# Page-3.net
KiCad netlist of a schematic drawn in Altium Designer
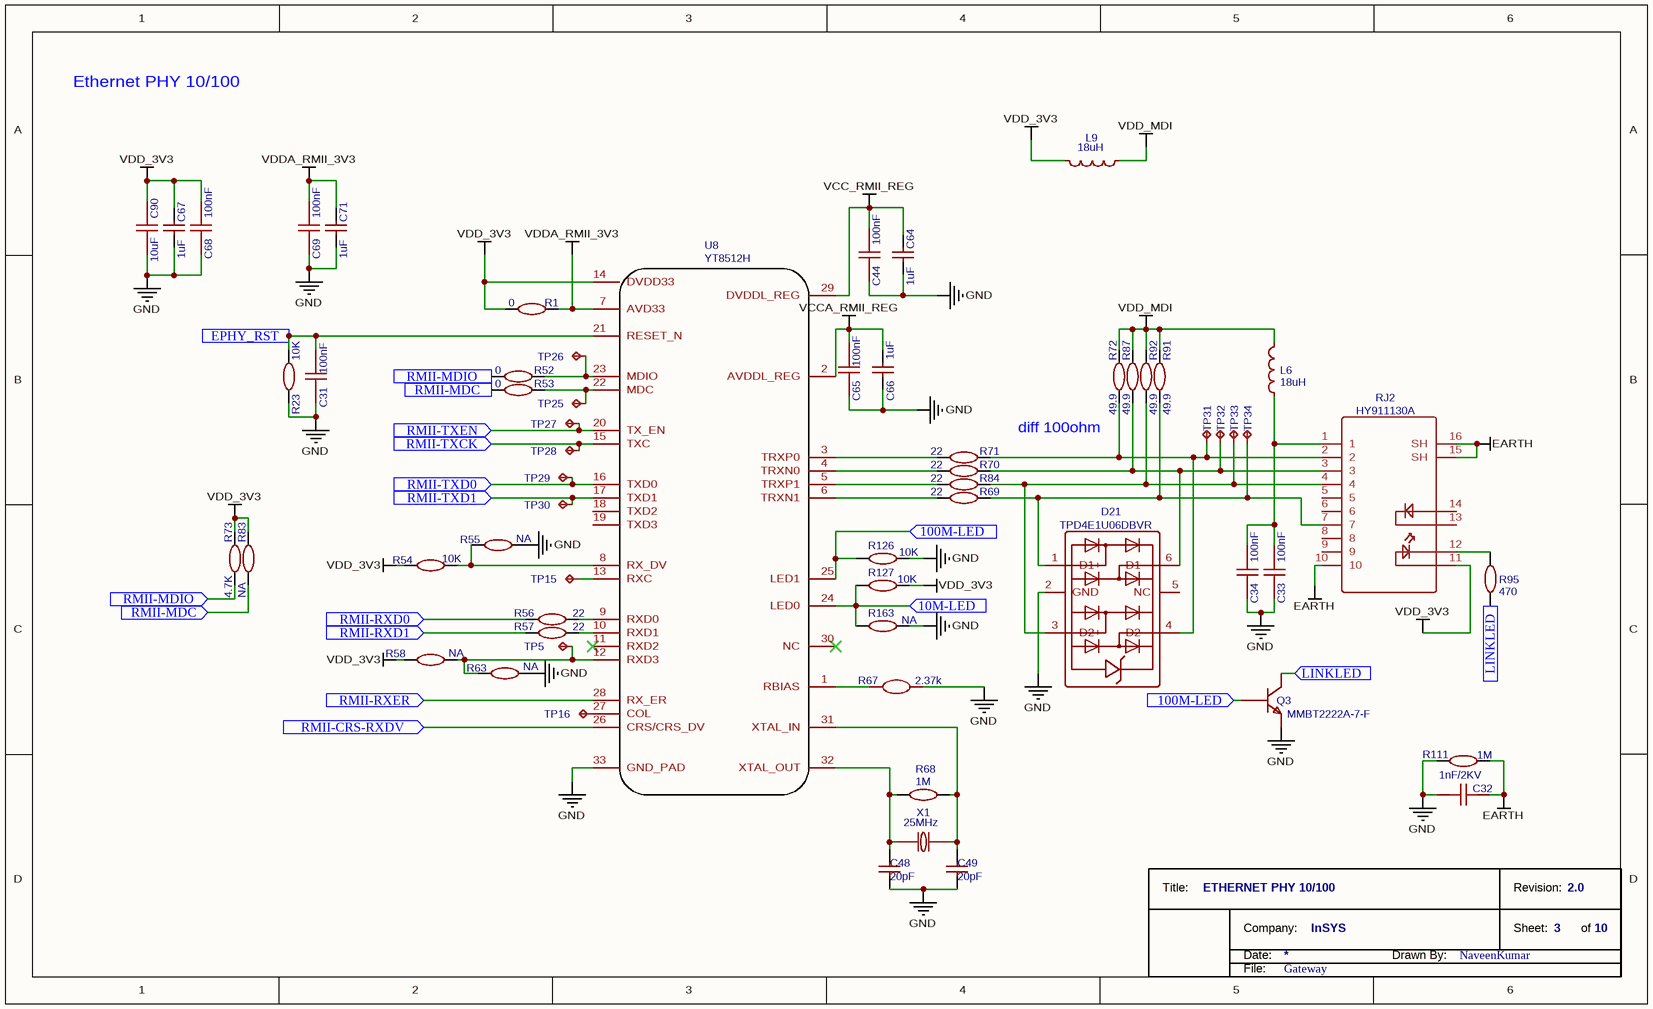
[diagram p0: Page-3.schdoc]

(export (version "E")
  (design (tool "Eeschema 10.0.6"))
  (components
    (comp (ref "*")
      (value "TitleBlock_1")
      (description "TitleBlock  No-2")
      (fields (field (name "DRAWN BY") "*"))
      (libsource (lib "GateWay_AllwinnerV2") (part "TitleBlock_1"))
    )
    (comp (ref "C31")
      (value "100nF")
      (footprint "GWAY_Capacitor_0603")
      (fields (field (name "MANUFACTURER") "SAMSUNG") (field (name "MANUFACTURER PART") "CL10B104KB8NNNC"))
      (libsource (lib "altium-import") (part "root_3_100nF_"))
    )
    (comp (ref "C32")
      (value "1nF/2KV")
      (footprint "GWAY_Capacitor_1206")
      (fields
        (field (name "MANUFACTURER") "Walsin Tech Corp")
        (field (name "MANUFACTURER PART") "1206B102K202CT")
        (field (name "CONTRIBUTOR") "LCSC")
      )
      (libsource (lib "altium-import") (part "root_0_1nF/2KV_"))
    )
    (comp (ref "C33")
      (value "100nF")
      (footprint "GWAY_Capacitor_0603")
      (fields (field (name "MANUFACTURER") "SAMSUNG") (field (name "MANUFACTURER PART") "CL10B104KB8NNNC"))
      (libsource (lib "altium-import") (part "root_3_100nF_"))
    )
    (comp (ref "C34")
      (value "100nF")
      (footprint "GWAY_Capacitor_0603")
      (fields (field (name "MANUFACTURER") "SAMSUNG") (field (name "MANUFACTURER PART") "CL10B104KB8NNNC"))
      (libsource (lib "altium-import") (part "root_3_100nF_"))
    )
    (comp (ref "C44")
      (value "100nF")
      (footprint "GWAY_Capacitor_0603")
      (fields (field (name "MANUFACTURER") "SAMSUNG") (field (name "MANUFACTURER PART") "CL10B104KB8NNNC"))
      (libsource (lib "altium-import") (part "root_3_100nF_"))
    )
    (comp (ref "C48")
      (value "20pF")
      (footprint "GWAY_Capacitor_0603")
      (fields (field (name "MANUFACTURER PART") "CL10C200JB8NNNC") (field (name "MANUFACTURER") "SAMSUNG"))
      (libsource (lib "altium-import") (part "root_1_20pF_"))
    )
    (comp (ref "C49")
      (value "20pF")
      (footprint "GWAY_Capacitor_0603")
      (fields (field (name "MANUFACTURER PART") "CL10C200JB8NNNC") (field (name "MANUFACTURER") "SAMSUNG"))
      (libsource (lib "altium-import") (part "root_1_20pF_"))
    )
    (comp (ref "C64")
      (value "1uF")
      (footprint "GWAY_Capacitor_0603")
      (fields
        (field (name "MANUFACTURER PART") "CL10B105KA8NNNC")
        (field (name "MANUFACTURER") "SAMSUNG(三星)")
      )
      (libsource (lib "altium-import") (part "root_3_1uF_"))
    )
    (comp (ref "C65")
      (value "100nF")
      (footprint "GWAY_Capacitor_0603")
      (fields (field (name "MANUFACTURER") "SAMSUNG") (field (name "MANUFACTURER PART") "CL10B104KB8NNNC"))
      (libsource (lib "altium-import") (part "root_3_100nF_"))
    )
    (comp (ref "C66")
      (value "1uF")
      (footprint "GWAY_Capacitor_0603")
      (fields (field (name "MANUFACTURER PART") "CL10A105KO8NNNC") (field (name "MANUFACTURER") "SAMSUNG"))
      (libsource (lib "altium-import") (part "root_1_1uF_"))
    )
    (comp (ref "C67")
      (value "1uF")
      (footprint "GWAY_Capacitor_0603")
      (fields
        (field (name "MANUFACTURER PART") "CL10B105KA8NNNC")
        (field (name "MANUFACTURER") "SAMSUNG(三星)")
      )
      (libsource (lib "altium-import") (part "root_3_1uF_"))
    )
    (comp (ref "C68")
      (value "100nF")
      (footprint "GWAY_Capacitor_0603")
      (fields (field (name "MANUFACTURER") "SAMSUNG") (field (name "MANUFACTURER PART") "CL10B104KB8NNNC"))
      (libsource (lib "altium-import") (part "root_3_100nF_"))
    )
    (comp (ref "C69")
      (value "100nF")
      (footprint "GWAY_Capacitor_0603")
      (fields (field (name "MANUFACTURER") "SAMSUNG") (field (name "MANUFACTURER PART") "CL10B104KB8NNNC"))
      (libsource (lib "altium-import") (part "root_3_100nF_"))
    )
    (comp (ref "C71")
      (value "1uF")
      (footprint "GWAY_Capacitor_0603")
      (fields
        (field (name "MANUFACTURER PART") "CL10B105KA8NNNC")
        (field (name "MANUFACTURER") "SAMSUNG(三星)")
      )
      (libsource (lib "altium-import") (part "root_3_1uF_"))
    )
    (comp (ref "C90")
      (value "10uF")
      (footprint "GWAY_Capacitor_0805")
      (fields
        (field (name "MANUFACTURER") "SAMSUNG(三星)")
        (field (name "MANUFACTURER PART") "CL21B106KOQNNNE")
      )
      (libsource (lib "altium-import") (part "root_1_10uF_"))
    )
    (comp (ref "D21")
      (value "TPD4E1U06DBVR")
      (footprint "GWAY_SOT23-6PIN")
      (fields (field (name "MANUFACTURER") "TI(德州仪器)") (field (name "CONTRIBUTOR") "LCSC"))
      (libsource (lib "altium-import") (part "root_3_TPD4E1U06DBVR_"))
    )
    (comp (ref "L6")
      (value "18uH")
      (footprint "GWAY_FerriteeBEAD_0805_C2012X105N")
      (fields (field (name "MANUFACTURER PART") "MLI2012-180") (field (name "MANUFACTURER") "ReliaPro"))
      (libsource (lib "altium-import") (part "root_1_18uH_"))
    )
    (comp (ref "L9")
      (value "18uH")
      (footprint "GWAY_FerriteeBEAD_0805_C2012X105N")
      (fields (field (name "MANUFACTURER PART") "MLI2012-180") (field (name "MANUFACTURER") "ReliaPro"))
      (libsource (lib "altium-import") (part "root_2_18uH_"))
    )
    (comp (ref "Q3")
      (value "MMBT2222A-7-F")
      (footprint "GWAY_SOT23-3PIN")
      (fields (field (name "MANUFACTURER") "DIODES(美台)") (field (name "CONTRIBUTOR") "LCSC"))
      (libsource (lib "altium-import") (part "root_0_MMBT2222A-7-F_"))
    )
    (comp (ref "R1")
      (value "0")
      (footprint "GWAY_Resistor_0603")
      (fields (field (name "MANUFACTURER") "YAGEO") (field (name "MANUFACTURER PART") "RC0603FR-070RL"))
      (libsource (lib "altium-import") (part "root_2_0_"))
    )
    (comp (ref "R23")
      (value "10K")
      (footprint "GWAY_Resistor_0603")
      (fields (field (name "MANUFACTURER") "YAGEO") (field (name "MANUFACTURER PART") "RC0603JR-0710KL"))
      (libsource (lib "altium-import") (part "root_3_10K_"))
    )
    (comp (ref "R52")
      (value "0")
      (footprint "GWAY_Resistor_0603")
      (fields (field (name "MANUFACTURER") "YAGEO") (field (name "MANUFACTURER PART") "RC0603FR-070RL"))
      (libsource (lib "altium-import") (part "root_2_0_"))
    )
    (comp (ref "R53")
      (value "0")
      (footprint "GWAY_Resistor_0603")
      (fields (field (name "MANUFACTURER") "YAGEO") (field (name "MANUFACTURER PART") "RC0603FR-070RL"))
      (libsource (lib "altium-import") (part "root_2_0_"))
    )
    (comp (ref "R54")
      (value "10K")
      (footprint "GWAY_Resistor_0603")
      (fields (field (name "MANUFACTURER") "YAGEO") (field (name "MANUFACTURER PART") "RC0603JR-0710KL"))
      (libsource (lib "altium-import") (part "root_0_10K_"))
    )
    (comp (ref "R55")
      (value "NA")
      (footprint "GWAY_Resistor_0603")
      (fields (field (name "MANUFACTURER") "YAGEO") (field (name "MANUFACTURER PART") "RC0603JR-0710KL"))
      (libsource (lib "altium-import") (part "root_0_NA_"))
    )
    (comp (ref "R56")
      (value "22")
      (footprint "GWAY_Resistor_0603")
      (fields (field (name "MANUFACTURER") "YAGEO") (field (name "MANUFACTURER PART") "RC0603FR-0722RL"))
      (libsource (lib "altium-import") (part "root_0_22_"))
    )
    (comp (ref "R57")
      (value "22")
      (footprint "GWAY_Resistor_0603")
      (fields (field (name "MANUFACTURER") "YAGEO") (field (name "MANUFACTURER PART") "RC0603FR-0722RL"))
      (libsource (lib "altium-import") (part "root_0_22_"))
    )
    (comp (ref "R58")
      (value "NA")
      (footprint "GWAY_Resistor_0603")
      (fields (field (name "MANUFACTURER") "YAGEO") (field (name "MANUFACTURER PART") "RC0603JR-0710KL"))
      (libsource (lib "altium-import") (part "root_0_NA_"))
    )
    (comp (ref "R63")
      (value "NA")
      (footprint "GWAY_Resistor_0603")
      (fields (field (name "MANUFACTURER") "YAGEO") (field (name "MANUFACTURER PART") "RC0603JR-0710KL"))
      (libsource (lib "altium-import") (part "root_0_NA_"))
    )
    (comp (ref "R67")
      (value "2.37k")
      (footprint "GWAY_Resistor_0603")
      (fields
        (field (name "MANUFACTURER") "YAGEO(国巨)")
        (field (name "MANUFACTURER PART") "RC0603FR-072K37L")
        (field (name "CONTRIBUTOR") "LCSC")
      )
      (libsource (lib "altium-import") (part "root_0_2.37k_"))
    )
    (comp (ref "R68")
      (value "1M")
      (footprint "GWAY_Resistor_0603")
      (fields (field (name "MANUFACTURER") "YAGEO(国巨)") (field (name "MANUFACTURER PART") "AC0603FR-071ML"))
      (libsource (lib "altium-import") (part "root_0_1M_"))
    )
    (comp (ref "R69")
      (value "22")
      (footprint "GWAY_Resistor_0603")
      (fields (field (name "MANUFACTURER") "YAGEO") (field (name "MANUFACTURER PART") "RC0603FR-0722RL"))
      (libsource (lib "altium-import") (part "root_0_22_"))
    )
    (comp (ref "R70")
      (value "22")
      (footprint "GWAY_Resistor_0603")
      (fields (field (name "MANUFACTURER") "YAGEO") (field (name "MANUFACTURER PART") "RC0603FR-0722RL"))
      (libsource (lib "altium-import") (part "root_0_22_"))
    )
    (comp (ref "R71")
      (value "22")
      (footprint "GWAY_Resistor_0603")
      (fields (field (name "MANUFACTURER") "YAGEO") (field (name "MANUFACTURER PART") "RC0603FR-0722RL"))
      (libsource (lib "altium-import") (part "root_0_22_"))
    )
    (comp (ref "R72")
      (value "49.9")
      (footprint "GWAY_Resistor_0603")
      (fields (field (name "MANUFACTURER") "YAGEO(国巨)") (field (name "MANUFACTURER PART") "RC0603FR-0749R9L"))
      (libsource (lib "altium-import") (part "root_1_49.9_"))
    )
    (comp (ref "R73")
      (value "4.7K")
      (footprint "GWAY_Resistor_0603")
      (fields (field (name "MANUFACTURER") "YAGEO(国巨)") (field (name "MANUFACTURER PART") "RC0603FR-074K7L"))
      (libsource (lib "altium-import") (part "root_1_4.7K_"))
    )
    (comp (ref "R83")
      (value "NA")
      (footprint "GWAY_Resistor_0603")
      (fields (field (name "MANUFACTURER") "YAGEO(国巨)") (field (name "MANUFACTURER PART") "RC0603FR-074K7L"))
      (libsource (lib "altium-import") (part "root_1_NA_"))
    )
    (comp (ref "R84")
      (value "22")
      (footprint "GWAY_Resistor_0603")
      (fields (field (name "MANUFACTURER") "YAGEO") (field (name "MANUFACTURER PART") "RC0603FR-0722RL"))
      (libsource (lib "altium-import") (part "root_0_22_"))
    )
    (comp (ref "R87")
      (value "49.9")
      (footprint "GWAY_Resistor_0603")
      (fields (field (name "MANUFACTURER") "YAGEO(国巨)") (field (name "MANUFACTURER PART") "RC0603FR-0749R9L"))
      (libsource (lib "altium-import") (part "root_1_49.9_"))
    )
    (comp (ref "R91")
      (value "49.9")
      (footprint "GWAY_Resistor_0603")
      (fields (field (name "MANUFACTURER") "YAGEO(国巨)") (field (name "MANUFACTURER PART") "RC0603FR-0749R9L"))
      (libsource (lib "altium-import") (part "root_1_49.9_"))
    )
    (comp (ref "R92")
      (value "49.9")
      (footprint "GWAY_Resistor_0603")
      (fields (field (name "MANUFACTURER") "YAGEO(国巨)") (field (name "MANUFACTURER PART") "RC0603FR-0749R9L"))
      (libsource (lib "altium-import") (part "root_1_49.9_"))
    )
    (comp (ref "R95")
      (value "470")
      (footprint "GWAY_Resistor_0603")
      (fields (field (name "MANUFACTURER") "YAGEO") (field (name "MANUFACTURER PART") "RC0603FR-07470RL"))
      (libsource (lib "altium-import") (part "root_1_470_"))
    )
    (comp (ref "R111")
      (value "1M")
      (footprint "GWAY_Resistor_0603")
      (fields (field (name "MANUFACTURER") "YAGEO") (field (name "MANUFACTURER PART") "RC0603FR-071ML"))
      (libsource (lib "altium-import") (part "root_0_1M_"))
    )
    (comp (ref "R126")
      (value "10K")
      (footprint "GWAY_Resistor_0603")
      (fields (field (name "MANUFACTURER") "YAGEO") (field (name "MANUFACTURER PART") "RC0603JR-0710KL"))
      (libsource (lib "altium-import") (part "root_0_10K_"))
    )
    (comp (ref "R127")
      (value "10K")
      (footprint "GWAY_Resistor_0603")
      (fields (field (name "MANUFACTURER") "YAGEO") (field (name "MANUFACTURER PART") "RC0603JR-0710KL"))
      (libsource (lib "altium-import") (part "root_0_10K_"))
    )
    (comp (ref "R163")
      (value "NA")
      (footprint "GWAY_Resistor_0603")
      (fields (field (name "MANUFACTURER") "YAGEO") (field (name "MANUFACTURER PART") "RC0603JR-0710KL"))
      (libsource (lib "altium-import") (part "root_0_NA_"))
    )
    (comp (ref "RJ2")
      (value "HY911130A")
      (footprint "GWay_HY911130AE")
      (fields (field (name "MANUFACTURER") "HANRUN(汉仁)"))
      (libsource (lib "altium-import") (part "root_0_HY911130A_"))
    )
    (comp (ref "TP5")
      (value "TP-052-TJ")
      (footprint "GWAY_TESTPOINT1")
      (fields (field (name "MANUFACTURER PART") "?"))
      (libsource (lib "altium-import") (part "root_1_TP-052-TJ_"))
    )
    (comp (ref "TP15")
      (value "TP-052-TJ")
      (footprint "GWAY_TESTPOINT1")
      (fields (field (name "MANUFACTURER PART") "?"))
      (libsource (lib "altium-import") (part "root_1_TP-052-TJ_"))
    )
    (comp (ref "TP16")
      (value "TP-052-TJ")
      (footprint "GWAY_TESTPOINT1")
      (fields (field (name "MANUFACTURER PART") "?"))
      (libsource (lib "altium-import") (part "root_1_TP-052-TJ_"))
    )
    (comp (ref "TP25")
      (value "TP-052-TJ")
      (footprint "GWAY_TESTPOINT1")
      (fields (field (name "MANUFACTURER PART") "?"))
      (libsource (lib "altium-import") (part "root_1_TP-052-TJ_"))
    )
    (comp (ref "TP26")
      (value "TP-052-TJ")
      (footprint "GWAY_TESTPOINT1")
      (fields (field (name "MANUFACTURER PART") "?"))
      (libsource (lib "altium-import") (part "root_1_TP-052-TJ_"))
    )
    (comp (ref "TP27")
      (value "TP-052-TJ")
      (footprint "GWAY_TESTPOINT1")
      (fields (field (name "MANUFACTURER PART") "?"))
      (libsource (lib "altium-import") (part "root_1_TP-052-TJ_"))
    )
    (comp (ref "TP28")
      (value "TP-052-TJ")
      (footprint "GWAY_TESTPOINT1")
      (fields (field (name "MANUFACTURER PART") "?"))
      (libsource (lib "altium-import") (part "root_1_TP-052-TJ_"))
    )
    (comp (ref "TP29")
      (value "TP-052-TJ")
      (footprint "GWAY_TESTPOINT1")
      (fields (field (name "MANUFACTURER PART") "?"))
      (libsource (lib "altium-import") (part "root_1_TP-052-TJ_"))
    )
    (comp (ref "TP30")
      (value "TP-052-TJ")
      (footprint "GWAY_TESTPOINT1")
      (fields (field (name "MANUFACTURER PART") "?"))
      (libsource (lib "altium-import") (part "root_1_TP-052-TJ_"))
    )
    (comp (ref "TP31")
      (value "TP-052-TJ")
      (footprint "GWAY_TESTPOINT1")
      (fields (field (name "MANUFACTURER PART") "?"))
      (libsource (lib "altium-import") (part "root_0_TP-052-TJ_"))
    )
    (comp (ref "TP32")
      (value "TP-052-TJ")
      (footprint "GWAY_TESTPOINT1")
      (fields (field (name "MANUFACTURER PART") "?"))
      (libsource (lib "altium-import") (part "root_0_TP-052-TJ_"))
    )
    (comp (ref "TP33")
      (value "TP-052-TJ")
      (footprint "GWAY_TESTPOINT1")
      (fields (field (name "MANUFACTURER PART") "?"))
      (libsource (lib "altium-import") (part "root_0_TP-052-TJ_"))
    )
    (comp (ref "TP34")
      (value "TP-052-TJ")
      (footprint "GWAY_TESTPOINT1")
      (fields (field (name "MANUFACTURER PART") "?"))
      (libsource (lib "altium-import") (part "root_0_TP-052-TJ_"))
    )
    (comp (ref "U8")
      (value "YT8512H")
      (footprint "GWAY_QFN_32Pin_5X5X1mm")
      (fields (field (name "CONTRIBUTOR") "orbeebabu"))
      (libsource (lib "altium-import") (part "root_0_YT8512H_"))
    )
    (comp (ref "X1")
      (value "25MHz")
      (footprint "GWAY_Crystal_SMD_HC49S")
      (fields (field (name "MANUFACTURER") "TXC") (field (name "MANUFACTURER PART") "9C2506LCSC-EEK2S"))
      (libsource (lib "altium-import") (part "root_0_25MHz_"))
    )
  )
  (nets
    (net (code "1") (name "/10M-LED") (class "Default")
      (node (ref "R127") (pin "1") (pinfunction "1_1") (pintype "passive"))
      (node (ref "R163") (pin "1") (pinfunction "1_1") (pintype "passive"))
      (node (ref "U8") (pin "24") (pinfunction "LED0_24") (pintype "passive"))
    )
    (net (code "2") (name "/100M-LED") (class "Default")
      (node (ref "Q3") (pin "1") (pinfunction "B_1") (pintype "passive"))
      (node (ref "R126") (pin "1") (pinfunction "1_1") (pintype "passive"))
      (node (ref "U8") (pin "25") (pinfunction "LED1_25") (pintype "passive"))
    )
    (net (code "3") (name "/EPHY_RST") (class "Default")
      (node (ref "C31") (pin "1") (pinfunction "1_1") (pintype "passive"))
      (node (ref "R23") (pin "1") (pinfunction "1_1") (pintype "passive"))
      (node (ref "U8") (pin "21") (pinfunction "RESET_N_21") (pintype "passive"))
    )
    (net (code "4") (name "/LINKLED") (class "Default")
      (node (ref "Q3") (pin "3") (pinfunction "C_3") (pintype "passive"))
      (node (ref "R95") (pin "1") (pinfunction "1_1") (pintype "passive"))
    )
    (net (code "5") (name "/RMII-CRS-RXDV") (class "Default")
      (node (ref "U8") (pin "26") (pinfunction "CRS/CRS_DV_26") (pintype "passive"))
    )
    (net (code "6") (name "/RMII-MDC") (class "Default")
      (node (ref "R53") (pin "2") (pinfunction "2_2") (pintype "passive"))
      (node (ref "R83") (pin "1") (pinfunction "1_1") (pintype "passive"))
    )
    (net (code "7") (name "/RMII-MDIO") (class "Default")
      (node (ref "R52") (pin "2") (pinfunction "2_2") (pintype "passive"))
      (node (ref "R73") (pin "1") (pinfunction "1_1") (pintype "passive"))
    )
    (net (code "8") (name "/RMII-RXD0") (class "Default")
      (node (ref "R56") (pin "1") (pinfunction "1_1") (pintype "passive"))
    )
    (net (code "9") (name "/RMII-RXD1") (class "Default")
      (node (ref "R57") (pin "1") (pinfunction "1_1") (pintype "passive"))
    )
    (net (code "10") (name "/RMII-RXER") (class "Default")
      (node (ref "U8") (pin "28") (pinfunction "RX_ER_28") (pintype "passive"))
    )
    (net (code "11") (name "/RMII-TXCK") (class "Default")
      (node (ref "TP28") (pin "1") (pinfunction "1_1") (pintype "passive"))
      (node (ref "U8") (pin "15") (pinfunction "TXC_15") (pintype "passive"))
    )
    (net (code "12") (name "/RMII-TXD0") (class "Default")
      (node (ref "TP29") (pin "1") (pinfunction "1_1") (pintype "passive"))
      (node (ref "U8") (pin "16") (pinfunction "TXD0_16") (pintype "passive"))
    )
    (net (code "13") (name "/RMII-TXD1") (class "Default")
      (node (ref "TP30") (pin "1") (pinfunction "1_1") (pintype "passive"))
      (node (ref "U8") (pin "17") (pinfunction "TXD1_17") (pintype "passive"))
    )
    (net (code "14") (name "/RMII-TXEN") (class "Default")
      (node (ref "TP27") (pin "1") (pinfunction "1_1") (pintype "passive"))
      (node (ref "U8") (pin "20") (pinfunction "TX_EN_20") (pintype "passive"))
    )
    (net (code "15") (name "EARTH") (class "Default")
      (node (ref "C32") (pin "1") (pinfunction "1_1") (pintype "passive"))
      (node (ref "R111") (pin "2") (pinfunction "2_2") (pintype "passive"))
      (node (ref "RJ2") (pin "10") (pinfunction "10_10") (pintype "passive"))
      (node (ref "RJ2") (pin "15") (pinfunction "SH_15") (pintype "passive"))
      (node (ref "RJ2") (pin "16") (pinfunction "SH_16") (pintype "passive"))
    )
    (net (code "16") (name "GND") (class "Default")
      (node (ref "C31") (pin "2") (pinfunction "2_2") (pintype "passive"))
      (node (ref "C32") (pin "2") (pinfunction "2_2") (pintype "passive"))
      (node (ref "C33") (pin "2") (pinfunction "2_2") (pintype "passive"))
      (node (ref "C34") (pin "2") (pinfunction "2_2") (pintype "passive"))
      (node (ref "C44") (pin "2") (pinfunction "2_2") (pintype "passive"))
      (node (ref "C48") (pin "1") (pinfunction "1_1") (pintype "passive"))
      (node (ref "C49") (pin "1") (pinfunction "1_1") (pintype "passive"))
      (node (ref "C64") (pin "2") (pinfunction "2_2") (pintype "passive"))
      (node (ref "C65") (pin "2") (pinfunction "2_2") (pintype "passive"))
      (node (ref "C66") (pin "1") (pinfunction "1_1") (pintype "passive"))
      (node (ref "C67") (pin "2") (pinfunction "2_2") (pintype "passive"))
      (node (ref "C68") (pin "2") (pinfunction "2_2") (pintype "passive"))
      (node (ref "C69") (pin "2") (pinfunction "2_2") (pintype "passive"))
      (node (ref "C71") (pin "2") (pinfunction "2_2") (pintype "passive"))
      (node (ref "C90") (pin "1") (pinfunction "1_1") (pintype "passive"))
      (node (ref "D21") (pin "2") (pinfunction "GND_2") (pintype "passive"))
      (node (ref "Q3") (pin "2") (pinfunction "E_2") (pintype "passive"))
      (node (ref "R111") (pin "1") (pinfunction "1_1") (pintype "passive"))
      (node (ref "R126") (pin "2") (pinfunction "2_2") (pintype "passive"))
      (node (ref "R163") (pin "2") (pinfunction "2_2") (pintype "passive"))
      (node (ref "R23") (pin "2") (pinfunction "2_2") (pintype "passive"))
      (node (ref "R55") (pin "2") (pinfunction "2_2") (pintype "passive"))
      (node (ref "R63") (pin "2") (pinfunction "2_2") (pintype "passive"))
      (node (ref "R67") (pin "2") (pinfunction "2_2") (pintype "passive"))
      (node (ref "U8") (pin "33") (pinfunction "GND_PAD_33") (pintype "passive"))
    )
    (net (code "17") (name "Net-(C33-Pad1)") (class "Default")
      (node (ref "C33") (pin "1") (pinfunction "1_1") (pintype "passive"))
      (node (ref "C34") (pin "1") (pinfunction "1_1") (pintype "passive"))
      (node (ref "L6") (pin "1") (pinfunction "1_1") (pintype "passive"))
      (node (ref "RJ2") (pin "1") (pinfunction "1_1") (pintype "passive"))
    )
    (net (code "18") (name "Net-(D21-D1+)") (class "Default")
      (node (ref "D21") (pin "1") (pinfunction "D1+_1") (pintype "passive"))
      (node (ref "R69") (pin "2") (pinfunction "2_2") (pintype "passive"))
      (node (ref "R91") (pin "1") (pinfunction "1_1") (pintype "passive"))
      (node (ref "RJ2") (pin "7") (pinfunction "7_7") (pintype "passive"))
      (node (ref "TP34") (pin "1") (pinfunction "1_1") (pintype "passive"))
    )
    (net (code "19") (name "Net-(D21-D1-)") (class "Default")
      (node (ref "D21") (pin "6") (pinfunction "D1-_6") (pintype "passive"))
      (node (ref "R70") (pin "2") (pinfunction "2_2") (pintype "passive"))
      (node (ref "R87") (pin "1") (pinfunction "1_1") (pintype "passive"))
      (node (ref "RJ2") (pin "3") (pinfunction "3_3") (pintype "passive"))
      (node (ref "TP32") (pin "1") (pinfunction "1_1") (pintype "passive"))
    )
    (net (code "20") (name "Net-(D21-D2+)") (class "Default")
      (node (ref "D21") (pin "3") (pinfunction "D2+_3") (pintype "passive"))
      (node (ref "R84") (pin "2") (pinfunction "2_2") (pintype "passive"))
      (node (ref "R92") (pin "1") (pinfunction "1_1") (pintype "passive"))
      (node (ref "RJ2") (pin "4") (pinfunction "4_4") (pintype "passive"))
      (node (ref "TP33") (pin "1") (pinfunction "1_1") (pintype "passive"))
    )
    (net (code "21") (name "Net-(D21-D2-)") (class "Default")
      (node (ref "D21") (pin "4") (pinfunction "D2-_4") (pintype "passive"))
      (node (ref "R71") (pin "2") (pinfunction "2_2") (pintype "passive"))
      (node (ref "R72") (pin "1") (pinfunction "1_1") (pintype "passive"))
      (node (ref "RJ2") (pin "2") (pinfunction "2_2") (pintype "passive"))
      (node (ref "TP31") (pin "1") (pinfunction "1_1") (pintype "passive"))
    )
    (net (code "22") (name "Net-(R95-Pad2)") (class "Default")
      (node (ref "R95") (pin "2") (pinfunction "2_2") (pintype "passive"))
      (node (ref "RJ2") (pin "12") (pinfunction "12_12") (pintype "passive"))
    )
    (net (code "23") (name "Net-(U8-COL)") (class "Default")
      (node (ref "TP16") (pin "1") (pinfunction "1_1") (pintype "passive"))
      (node (ref "U8") (pin "27") (pinfunction "COL_27") (pintype "passive"))
    )
    (net (code "24") (name "Net-(U8-MDC)") (class "Default")
      (node (ref "R53") (pin "1") (pinfunction "1_1") (pintype "passive"))
      (node (ref "TP25") (pin "1") (pinfunction "1_1") (pintype "passive"))
      (node (ref "U8") (pin "22") (pinfunction "MDC_22") (pintype "passive"))
    )
    (net (code "25") (name "Net-(U8-MDIO)") (class "Default")
      (node (ref "R52") (pin "1") (pinfunction "1_1") (pintype "passive"))
      (node (ref "TP26") (pin "1") (pinfunction "1_1") (pintype "passive"))
      (node (ref "U8") (pin "23") (pinfunction "MDIO_23") (pintype "passive"))
    )
    (net (code "26") (name "Net-(U8-RBIAS)") (class "Default")
      (node (ref "R67") (pin "1") (pinfunction "1_1") (pintype "passive"))
      (node (ref "U8") (pin "1") (pinfunction "RBIAS_1") (pintype "passive"))
    )
    (net (code "27") (name "Net-(U8-RXC)") (class "Default")
      (node (ref "TP15") (pin "1") (pinfunction "1_1") (pintype "passive"))
      (node (ref "U8") (pin "13") (pinfunction "RXC_13") (pintype "passive"))
    )
    (net (code "28") (name "Net-(U8-RXD0)") (class "Default")
      (node (ref "R56") (pin "2") (pinfunction "2_2") (pintype "passive"))
      (node (ref "U8") (pin "9") (pinfunction "RXD0_9") (pintype "passive"))
    )
    (net (code "29") (name "Net-(U8-RXD1)") (class "Default")
      (node (ref "R57") (pin "2") (pinfunction "2_2") (pintype "passive"))
      (node (ref "U8") (pin "10") (pinfunction "RXD1_10") (pintype "passive"))
    )
    (net (code "30") (name "Net-(U8-RXD3)") (class "Default")
      (node (ref "R58") (pin "2") (pinfunction "2_2") (pintype "passive"))
      (node (ref "R63") (pin "1") (pinfunction "1_1") (pintype "passive"))
      (node (ref "TP5") (pin "1") (pinfunction "1_1") (pintype "passive"))
      (node (ref "U8") (pin "12") (pinfunction "RXD3_12") (pintype "passive"))
    )
    (net (code "31") (name "Net-(U8-RX_DV)") (class "Default")
      (node (ref "R54") (pin "2") (pinfunction "2_2") (pintype "passive"))
      (node (ref "R55") (pin "1") (pinfunction "1_1") (pintype "passive"))
      (node (ref "U8") (pin "8") (pinfunction "RX_DV_8") (pintype "passive"))
    )
    (net (code "32") (name "Net-(U8-TRXN0)") (class "Default")
      (node (ref "R70") (pin "1") (pinfunction "1_1") (pintype "passive"))
      (node (ref "U8") (pin "4") (pinfunction "TRXN0_4") (pintype "passive"))
    )
    (net (code "33") (name "Net-(U8-TRXN1)") (class "Default")
      (node (ref "R69") (pin "1") (pinfunction "1_1") (pintype "passive"))
      (node (ref "U8") (pin "6") (pinfunction "TRXN1_6") (pintype "passive"))
    )
    (net (code "34") (name "Net-(U8-TRXP0)") (class "Default")
      (node (ref "R71") (pin "1") (pinfunction "1_1") (pintype "passive"))
      (node (ref "U8") (pin "3") (pinfunction "TRXP0_3") (pintype "passive"))
    )
    (net (code "35") (name "Net-(U8-TRXP1)") (class "Default")
      (node (ref "R84") (pin "1") (pinfunction "1_1") (pintype "passive"))
      (node (ref "U8") (pin "5") (pinfunction "TRXP1_5") (pintype "passive"))
    )
    (net (code "36") (name "Net-(U8-XTAL_IN)") (class "Default")
      (node (ref "C49") (pin "2") (pinfunction "2_2") (pintype "passive"))
      (node (ref "R68") (pin "2") (pinfunction "2_2") (pintype "passive"))
      (node (ref "U8") (pin "31") (pinfunction "XTAL_IN_31") (pintype "passive"))
      (node (ref "X1") (pin "2") (pinfunction "2_2") (pintype "passive"))
    )
    (net (code "37") (name "Net-(U8-XTAL_OUT)") (class "Default")
      (node (ref "C48") (pin "2") (pinfunction "2_2") (pintype "passive"))
      (node (ref "R68") (pin "1") (pinfunction "1_1") (pintype "passive"))
      (node (ref "U8") (pin "32") (pinfunction "XTAL_OUT_32") (pintype "passive"))
      (node (ref "X1") (pin "1") (pinfunction "1_1") (pintype "passive"))
    )
    (net (code "38") (name "VCCA_RMII_REG") (class "Default")
      (node (ref "C65") (pin "1") (pinfunction "1_1") (pintype "passive"))
      (node (ref "C66") (pin "2") (pinfunction "2_2") (pintype "passive"))
      (node (ref "U8") (pin "2") (pinfunction "AVDDL_REG_2") (pintype "passive"))
    )
    (net (code "39") (name "VCC_RMII_REG") (class "Default")
      (node (ref "C44") (pin "1") (pinfunction "1_1") (pintype "passive"))
      (node (ref "C64") (pin "1") (pinfunction "1_1") (pintype "passive"))
      (node (ref "U8") (pin "29") (pinfunction "DVDDL_REG_29") (pintype "passive"))
    )
    (net (code "40") (name "VDDA_RMII_3V3") (class "Default")
      (node (ref "C69") (pin "1") (pinfunction "1_1") (pintype "passive"))
      (node (ref "C71") (pin "1") (pinfunction "1_1") (pintype "passive"))
      (node (ref "R1") (pin "1") (pinfunction "1_1") (pintype "passive"))
      (node (ref "U8") (pin "7") (pinfunction "AVD33_7") (pintype "passive"))
    )
    (net (code "41") (name "VDD_3V3") (class "Default")
      (node (ref "C67") (pin "1") (pinfunction "1_1") (pintype "passive"))
      (node (ref "C68") (pin "1") (pinfunction "1_1") (pintype "passive"))
      (node (ref "C90") (pin "2") (pinfunction "2_2") (pintype "passive"))
      (node (ref "L9") (pin "2") (pinfunction "2_2") (pintype "passive"))
      (node (ref "R1") (pin "2") (pinfunction "2_2") (pintype "passive"))
      (node (ref "R127") (pin "2") (pinfunction "2_2") (pintype "passive"))
      (node (ref "R54") (pin "1") (pinfunction "1_1") (pintype "passive"))
      (node (ref "R58") (pin "1") (pinfunction "1_1") (pintype "passive"))
      (node (ref "R73") (pin "2") (pinfunction "2_2") (pintype "passive"))
      (node (ref "R83") (pin "2") (pinfunction "2_2") (pintype "passive"))
      (node (ref "RJ2") (pin "11") (pinfunction "11_11") (pintype "passive"))
      (node (ref "U8") (pin "14") (pinfunction "DVDD33_14") (pintype "passive"))
    )
    (net (code "42") (name "VDD_MDI") (class "Default")
      (node (ref "L6") (pin "2") (pinfunction "2_2") (pintype "passive"))
      (node (ref "L9") (pin "1") (pinfunction "1_1") (pintype "passive"))
      (node (ref "R72") (pin "2") (pinfunction "2_2") (pintype "passive"))
      (node (ref "R87") (pin "2") (pinfunction "2_2") (pintype "passive"))
      (node (ref "R91") (pin "2") (pinfunction "2_2") (pintype "passive"))
      (node (ref "R92") (pin "2") (pinfunction "2_2") (pintype "passive"))
    )
    (net (code "43") (name "unconnected-(D21-NC-Pad5)") (class "Default")
      (node (ref "D21") (pin "5") (pinfunction "NC_5") (pintype "passive"))
    )
    (net (code "44") (name "unconnected-(RJ2-Pad5)") (class "Default")
      (node (ref "RJ2") (pin "5") (pinfunction "5_5") (pintype "passive"))
    )
    (net (code "45") (name "unconnected-(RJ2-Pad6)") (class "Default")
      (node (ref "RJ2") (pin "6") (pinfunction "6_6") (pintype "passive"))
    )
    (net (code "46") (name "unconnected-(RJ2-Pad8)") (class "Default")
      (node (ref "RJ2") (pin "8") (pinfunction "8_8") (pintype "passive"))
    )
    (net (code "47") (name "unconnected-(RJ2-Pad9)") (class "Default")
      (node (ref "RJ2") (pin "9") (pinfunction "9_9") (pintype "passive"))
    )
    (net (code "48") (name "unconnected-(RJ2-Pad13)") (class "Default")
      (node (ref "RJ2") (pin "13") (pinfunction "13_13") (pintype "passive"))
    )
    (net (code "49") (name "unconnected-(RJ2-Pad14)") (class "Default")
      (node (ref "RJ2") (pin "14") (pinfunction "14_14") (pintype "passive"))
    )
    (net (code "50") (name "unconnected-(U8-NC-Pad30)") (class "Default")
      (node (ref "U8") (pin "30") (pinfunction "NC_30") (pintype "passive+no_connect"))
    )
    (net (code "51") (name "unconnected-(U8-RXD2-Pad11)") (class "Default")
      (node (ref "U8") (pin "11") (pinfunction "RXD2_11") (pintype "passive+no_connect"))
    )
    (net (code "52") (name "unconnected-(U8-TXD2-Pad18)") (class "Default")
      (node (ref "U8") (pin "18") (pinfunction "TXD2_18") (pintype "passive"))
    )
    (net (code "53") (name "unconnected-(U8-TXD3-Pad19)") (class "Default")
      (node (ref "U8") (pin "19") (pinfunction "TXD3_19") (pintype "passive"))
    )
  )
)
